# PA_stage_1.net
KiCad netlist of a schematic drawn in Altium Designer
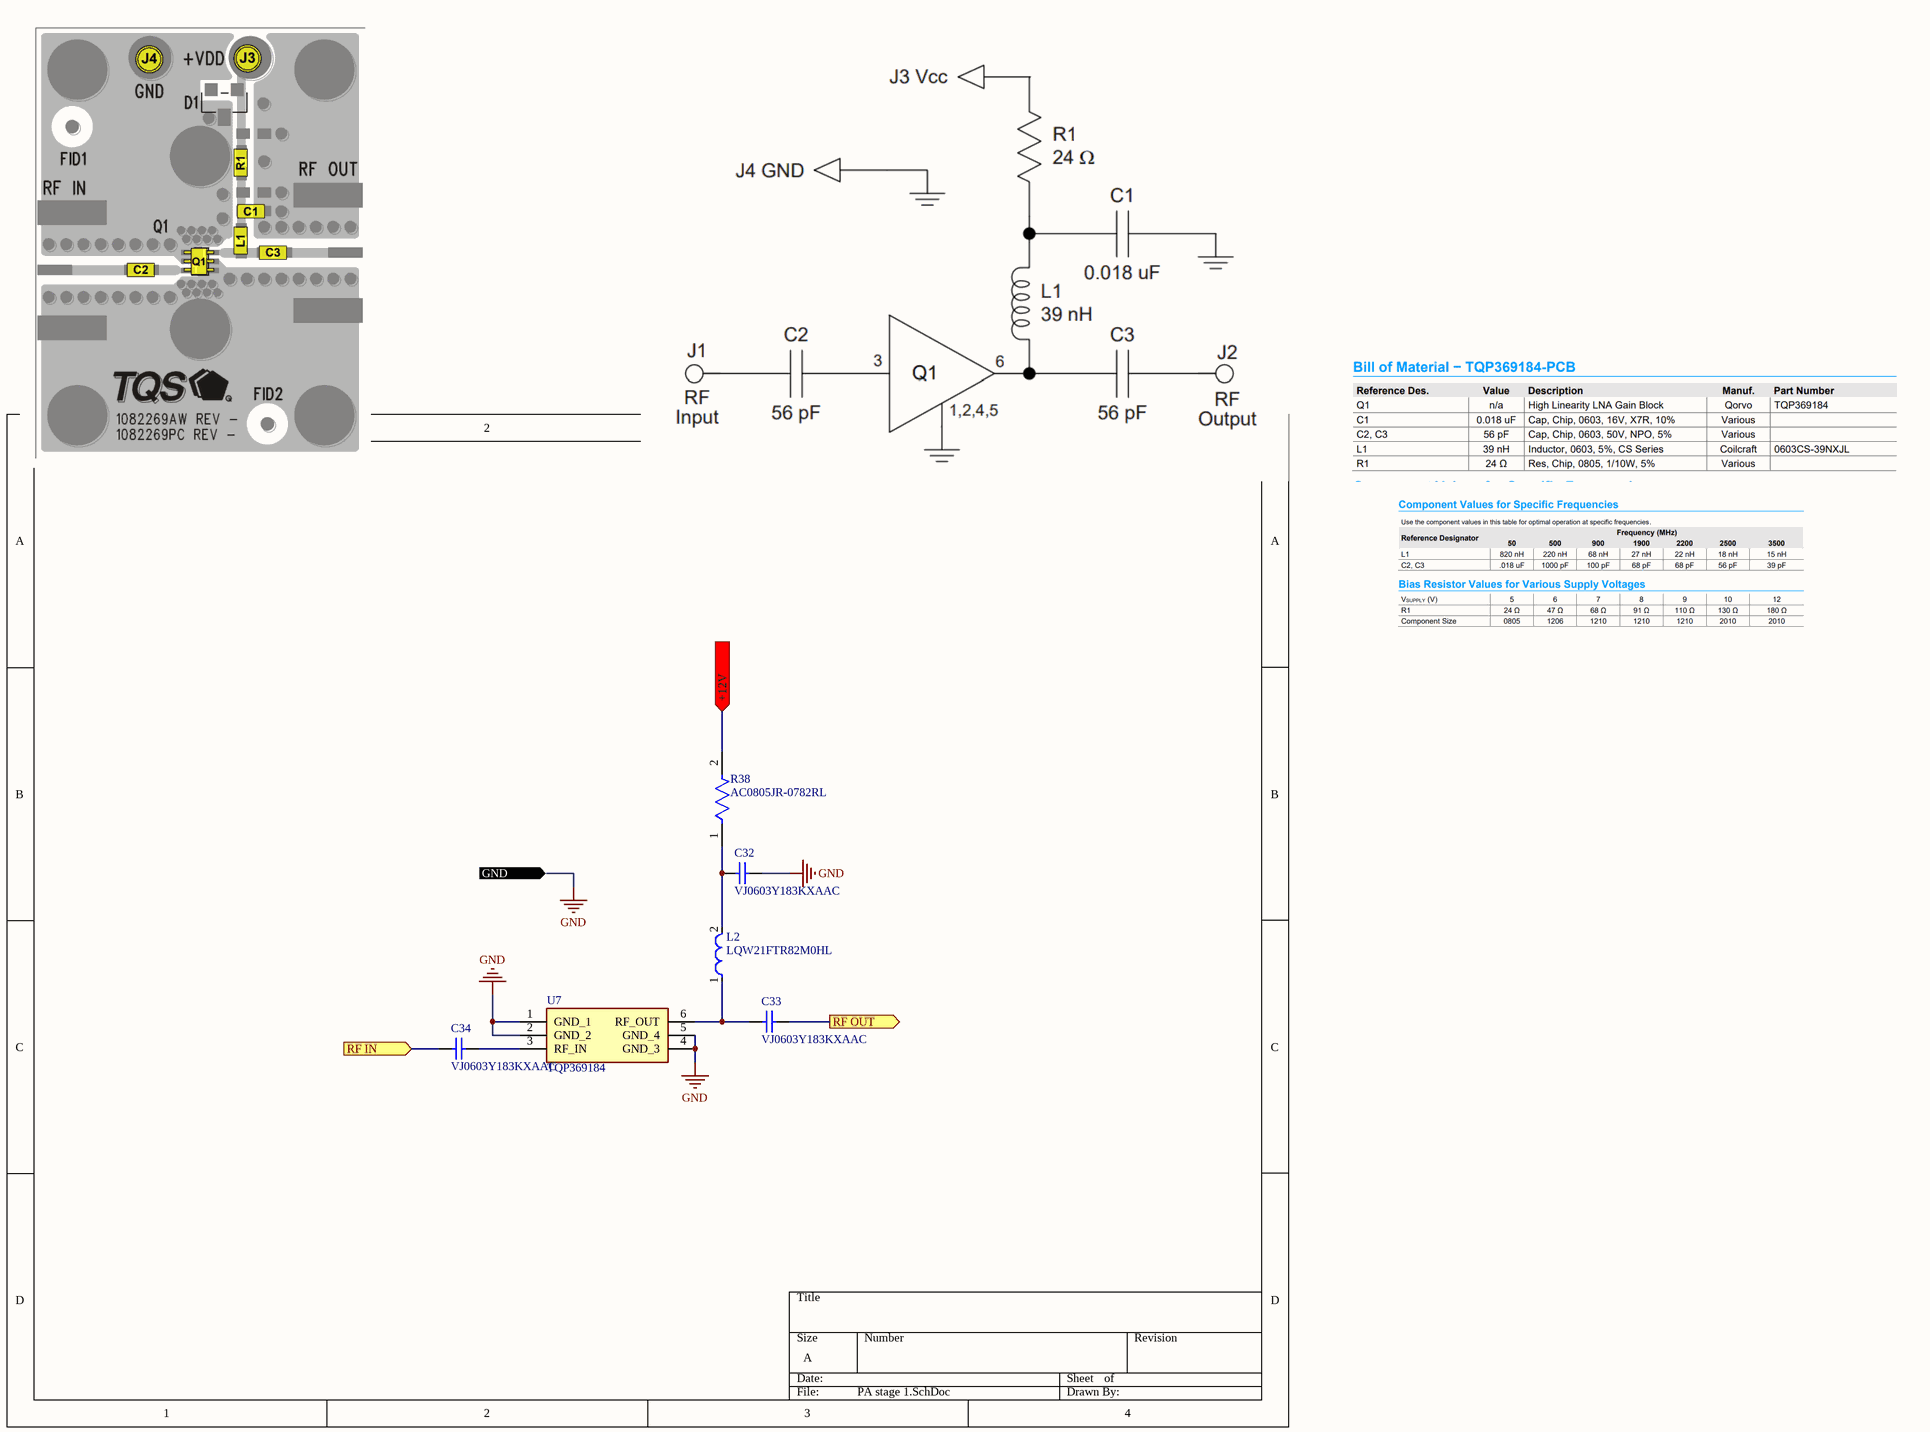
[diagram p0: PA stage 1.SchDoc]

(export (version "E")
  (design (tool "Eeschema 10.0.6"))
  (components
    (comp (ref "C32")
      (value "VJ0603Y183KXAAC")
      (footprint "CAPC1608X92X38ML15T08")
      (fields (field (name "MANUFACTURER") "Vitramon"))
      (libsource (lib "Altium Content Vault") (part "CAP"))
    )
    (comp (ref "C33")
      (value "VJ0603Y183KXAAC")
      (footprint "CAPC1608X92X38ML15T08")
      (fields (field (name "MANUFACTURER") "Vitramon"))
      (libsource (lib "Altium Content Vault") (part "CAP"))
    )
    (comp (ref "C34")
      (value "VJ0603Y183KXAAC")
      (footprint "CAPC1608X92X38ML15T08")
      (fields (field (name "MANUFACTURER") "Vitramon"))
      (libsource (lib "Altium Content Vault") (part "CAP"))
    )
    (comp (ref "L2")
      (value "LQW21FTR82M0HL")
      (footprint "FP-LQW21FT_0H-MFG")
      (description "FIXED IND 1UH 700MA POWRTRN")
      (libsource (lib "Altium Content Vault") (part "725321dda6339637d4d059423bc1c3c"))
    )
    (comp (ref "R38")
      (value "AC0805JR-0782RL")
      (footprint "FP-AC0805-MFG")
      (description "RES SMD 82 OHM 5% 1/8W 0805")
      (fields (field (name "TOLERANCE") "0.05") (field (name "MANUFACTURER") "Yageo"))
      (libsource (lib "Altium Content Vault") (part "1029c3af85768c4190bb7ad29bc67b5"))
    )
    (comp (ref "U7")
      (value "TQP369184")
      (footprint "SOT65P210X110-6N")
      (description "DC  6 GHz Gain Block")
      (fields (field (name "MOUSER PART NUMBER") "772-TQP369184"))
      (libsource (lib "TQP369184") (part "TQP369184"))
    )
  )
  (nets
    (net (code "1") (name "/+12V") (class "Default")
      (node (ref "R38") (pin "2") (pinfunction "2_2") (pintype "passive"))
    )
    (net (code "2") (name "/RF IN") (class "Default")
      (node (ref "C34") (pin "1") (pinfunction "1_1") (pintype "passive"))
    )
    (net (code "3") (name "/RF OUT") (class "Default")
      (node (ref "C33") (pin "2") (pinfunction "2_2") (pintype "passive"))
    )
    (net (code "4") (name "GND") (class "Default")
      (node (ref "C32") (pin "2") (pinfunction "2_2") (pintype "passive"))
      (node (ref "U7") (pin "1") (pinfunction "GND_1_1") (pintype "passive"))
      (node (ref "U7") (pin "2") (pinfunction "GND_2_2") (pintype "passive"))
      (node (ref "U7") (pin "4") (pinfunction "GND_3_4") (pintype "passive"))
      (node (ref "U7") (pin "5") (pinfunction "GND_4_5") (pintype "passive"))
    )
    (net (code "5") (name "Net-(C32-Pad1)") (class "Default")
      (node (ref "C32") (pin "1") (pinfunction "1_1") (pintype "passive"))
      (node (ref "L2") (pin "2") (pinfunction "2_2") (pintype "passive"))
      (node (ref "R38") (pin "1") (pinfunction "1_1") (pintype "passive"))
    )
    (net (code "6") (name "Net-(U7-RF_IN)") (class "Default")
      (node (ref "C34") (pin "2") (pinfunction "2_2") (pintype "passive"))
      (node (ref "U7") (pin "3") (pinfunction "RF_IN_3") (pintype "passive"))
    )
    (net (code "7") (name "Net-(U7-RF_OUT)") (class "Default")
      (node (ref "C33") (pin "1") (pinfunction "1_1") (pintype "passive"))
      (node (ref "L2") (pin "1") (pinfunction "1_1") (pintype "passive"))
      (node (ref "U7") (pin "6") (pinfunction "RF_OUT_6") (pintype "passive"))
    )
  )
)
